# ES_Project.net
KiCad netlist of a schematic drawn in EasyEDA
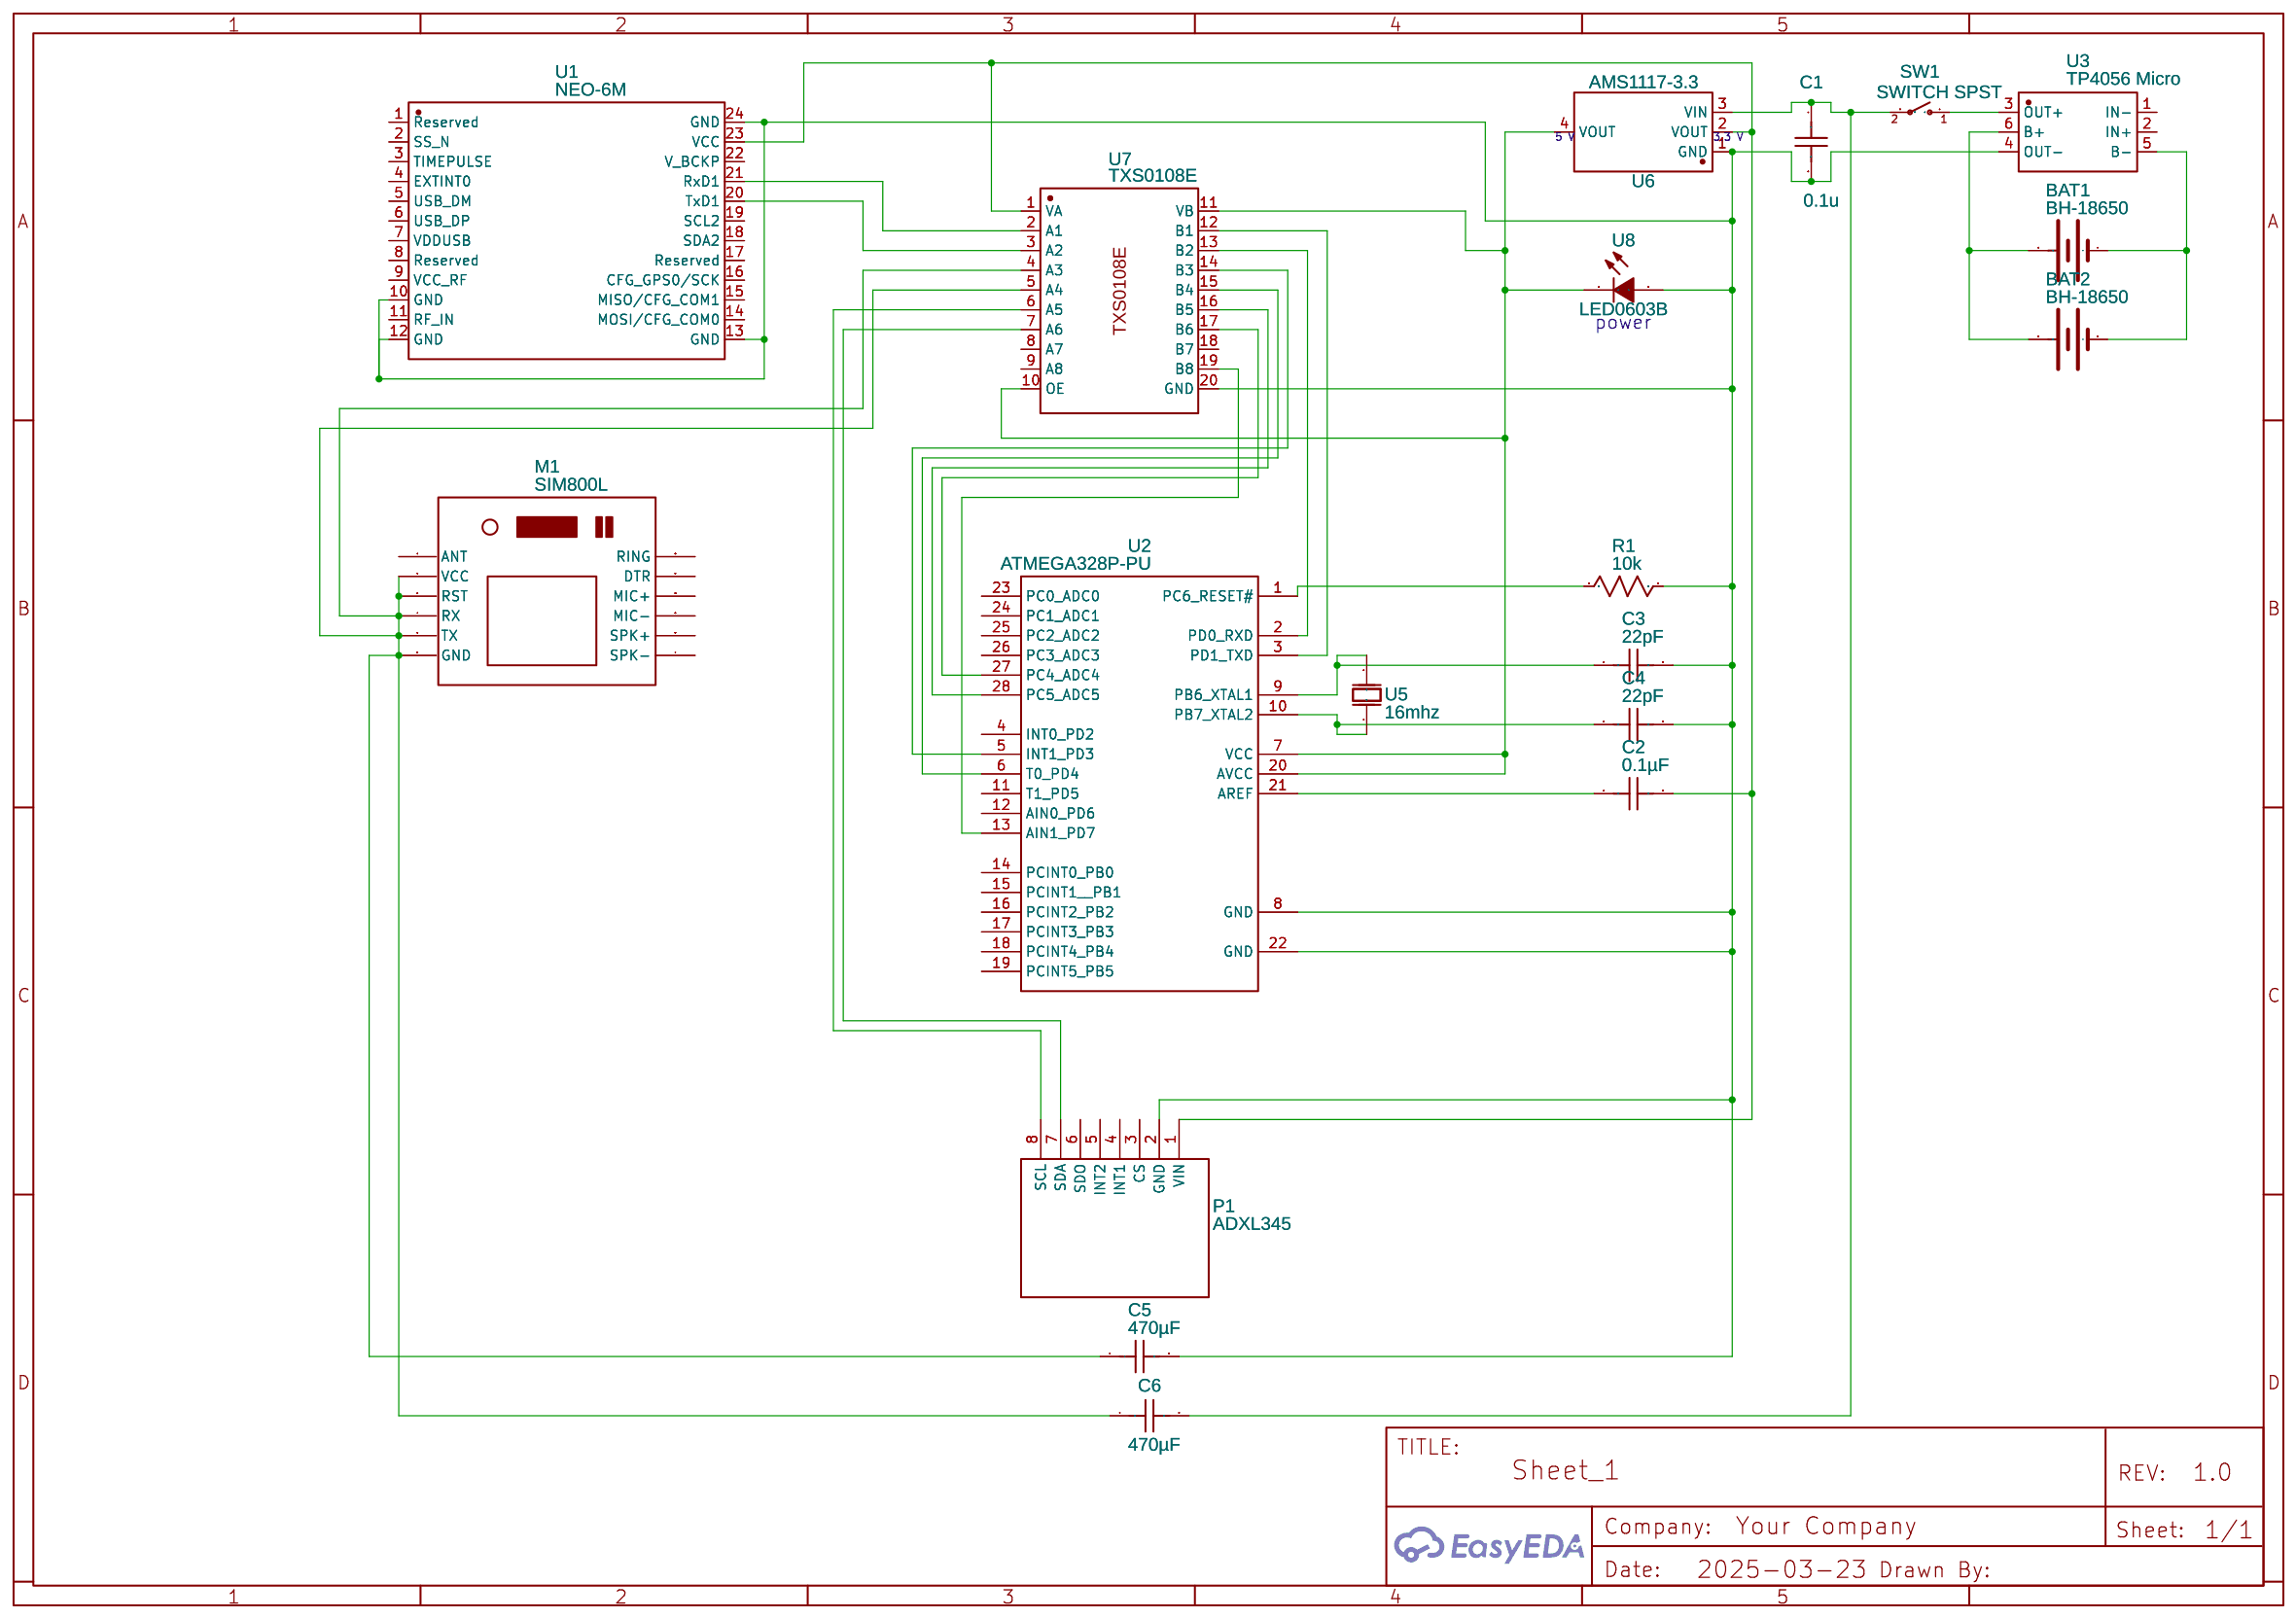
[diagram p0: schematic sheet]

(export (version "E")
  (design (tool "Eeschema 10.0.6"))
  (components
    (comp (ref "BAT1") (value "BH-18650") (libsource (lib "") (part "BH-18650")))
    (comp (ref "BAT2") (value "BH-18650") (libsource (lib "") (part "BH-18650")))
    (comp (ref "C1") (value "0.1u") (libsource (lib "") (part "C_0603_US_1")))
    (comp (ref "C2") (value "0.1µF") (libsource (lib "") (part "C_0603_US")))
    (comp (ref "C3") (value "22pF") (libsource (lib "") (part "C_0603_US")))
    (comp (ref "C4") (value "22pF") (libsource (lib "") (part "C_0603_US")))
    (comp (ref "C5") (value "470µF") (libsource (lib "") (part "C_0603_US")))
    (comp (ref "C6") (value "470µF") (libsource (lib "") (part "C_0603_US")))
    (comp (ref "M1") (value "SIM800L") (libsource (lib "") (part "SIM800L")))
    (comp (ref "P1") (value "ADXL345") (libsource (lib "") (part "ADXL345")))
    (comp (ref "R1") (value "10k") (libsource (lib "") (part "R_0603_US")))
    (comp (ref "SW1") (value "SWITCH SPST") (libsource (lib "") (part "SWITCH SPST")))
    (comp (ref "U1") (value "NEO-6M") (libsource (lib "") (part "NEO-6M")))
    (comp (ref "U2")
      (value "ATMEGA328P-PU")
      (fields (field (name "Manufacturer") "MICROCHIP(美国微芯)"))
      (libsource (lib "") (part "ATMEGA328P-PU"))
    )
    (comp (ref "U3") (value "TP4056 Micro") (libsource (lib "") (part "TP4056 Micro")))
    (comp (ref "U5") (value "16mhz") (libsource (lib "") (part "16MHZCRYSTAL")))
    (comp (ref "U6")
      (value "AMS1117-3.3")
      (fields (field (name "Manufacturer") "AMS"))
      (libsource (lib "") (part "AMS1117-3.3"))
    )
    (comp (ref "U7") (value "TXS0108E") (libsource (lib "") (part "TXS0108E")))
    (comp (ref "U8") (value "LED0603B") (libsource (lib "") (part "LED0603B")))
  )
  (nets
    (net (code "1") (name "Net-(BAT1-+)") (class "Default")
      (node (ref "BAT1") (pin "2") (pinfunction "+_2") (pintype "passive"))
      (node (ref "BAT2") (pin "2") (pinfunction "+_2") (pintype "passive"))
      (node (ref "U3") (pin "6") (pinfunction "B+_6") (pintype "output"))
    )
    (net (code "2") (name "Net-(BAT1--)") (class "Default")
      (node (ref "BAT1") (pin "1") (pinfunction "-_1") (pintype "passive"))
      (node (ref "BAT2") (pin "1") (pinfunction "-_1") (pintype "passive"))
      (node (ref "U3") (pin "5") (pinfunction "B-_5") (pintype "output"))
    )
    (net (code "3") (name "Net-(M1-GND)") (class "Default")
      (node (ref "C5") (pin "1") (pinfunction "1_1") (pintype "unspecified"))
      (node (ref "C6") (pin "1") (pinfunction "1_1") (pintype "unspecified"))
      (node (ref "M1") (pin "2") (pinfunction "VCC_2") (pintype "input"))
      (node (ref "M1") (pin "3") (pinfunction "RST_3") (pintype "input"))
      (node (ref "M1") (pin "4") (pinfunction "RX_4") (pintype "input"))
      (node (ref "M1") (pin "5") (pinfunction "TX_5") (pintype "output"))
      (node (ref "M1") (pin "6") (pinfunction "GND_6") (pintype "output"))
      (node (ref "U7") (pin "4") (pinfunction "A3_4") (pintype "unspecified"))
      (node (ref "U7") (pin "5") (pinfunction "A4_5") (pintype "unspecified"))
    )
    (net (code "4") (name "Net-(P1-GND)") (class "Default")
      (node (ref "C1") (pin "2") (pinfunction "2_2") (pintype "unspecified"))
      (node (ref "C3") (pin "2") (pinfunction "2_2") (pintype "unspecified"))
      (node (ref "C4") (pin "2") (pinfunction "2_2") (pintype "unspecified"))
      (node (ref "C5") (pin "2") (pinfunction "2_2") (pintype "unspecified"))
      (node (ref "P1") (pin "2") (pinfunction "GND_2") (pintype "unspecified"))
      (node (ref "R1") (pin "2") (pinfunction "2_2") (pintype "unspecified"))
      (node (ref "U1") (pin "10") (pinfunction "GND_10") (pintype "unspecified"))
      (node (ref "U1") (pin "12") (pinfunction "GND_12") (pintype "unspecified"))
      (node (ref "U1") (pin "13") (pinfunction "GND_13") (pintype "unspecified"))
      (node (ref "U1") (pin "24") (pinfunction "GND_24") (pintype "unspecified"))
      (node (ref "U2") (pin "22") (pinfunction "GND_22") (pintype "passive"))
      (node (ref "U2") (pin "8") (pinfunction "GND_8") (pintype "passive"))
      (node (ref "U3") (pin "4") (pinfunction "OUT-_4") (pintype "output"))
      (node (ref "U6") (pin "1") (pinfunction "GND_1") (pintype "unspecified"))
      (node (ref "U7") (pin "20") (pinfunction "GND_20") (pintype "unspecified"))
      (node (ref "U8") (pin "2") (pinfunction "A_2") (pintype "input"))
    )
    (net (code "5") (name "Net-(P1-SCL)") (class "Default")
      (node (ref "P1") (pin "8") (pinfunction "SCL_8") (pintype "unspecified"))
      (node (ref "U7") (pin "6") (pinfunction "A5_6") (pintype "unspecified"))
    )
    (net (code "6") (name "Net-(P1-SDA)") (class "Default")
      (node (ref "P1") (pin "7") (pinfunction "SDA_7") (pintype "unspecified"))
      (node (ref "U7") (pin "7") (pinfunction "A6_7") (pintype "unspecified"))
    )
    (net (code "7") (name "Net-(P1-VIN)") (class "Default")
      (node (ref "C2") (pin "2") (pinfunction "2_2") (pintype "unspecified"))
      (node (ref "P1") (pin "1") (pinfunction "VIN_1") (pintype "unspecified"))
      (node (ref "U1") (pin "23") (pinfunction "VCC_23") (pintype "unspecified"))
      (node (ref "U6") (pin "2") (pinfunction "VOUT_2") (pintype "unspecified"))
      (node (ref "U7") (pin "1") (pinfunction "VA_1") (pintype "unspecified"))
    )
    (net (code "8") (name "Net-(U1-RxD1)") (class "Default")
      (node (ref "U1") (pin "21") (pinfunction "RxD1_21") (pintype "unspecified"))
      (node (ref "U7") (pin "2") (pinfunction "A1_2") (pintype "unspecified"))
    )
    (net (code "9") (name "Net-(U1-TxD1)") (class "Default")
      (node (ref "U1") (pin "20") (pinfunction "TxD1_20") (pintype "unspecified"))
      (node (ref "U7") (pin "3") (pinfunction "A2_3") (pintype "unspecified"))
    )
    (net (code "10") (name "Net-(U2-AIN1_PD7)") (class "Default")
      (node (ref "U2") (pin "13") (pinfunction "AIN1_PD7_13") (pintype "bidirectional"))
      (node (ref "U7") (pin "19") (pinfunction "B8_19") (pintype "unspecified"))
    )
    (net (code "11") (name "Net-(U2-AREF)") (class "Default")
      (node (ref "C2") (pin "1") (pinfunction "1_1") (pintype "unspecified"))
      (node (ref "U2") (pin "21") (pinfunction "AREF_21") (pintype "passive"))
    )
    (net (code "12") (name "Net-(U2-AVCC)") (class "Default")
      (node (ref "U2") (pin "20") (pinfunction "AVCC_20") (pintype "passive"))
      (node (ref "U2") (pin "7") (pinfunction "VCC_7") (pintype "passive"))
      (node (ref "U6") (pin "4") (pinfunction "VOUT_4") (pintype "unspecified"))
      (node (ref "U7") (pin "10") (pinfunction "OE_10") (pintype "unspecified"))
      (node (ref "U7") (pin "11") (pinfunction "VB_11") (pintype "unspecified"))
      (node (ref "U8") (pin "1") (pinfunction "K_1") (pintype "input"))
    )
    (net (code "13") (name "Net-(U2-INT1_PD3)") (class "Default")
      (node (ref "U2") (pin "5") (pinfunction "INT1_PD3_5") (pintype "bidirectional"))
      (node (ref "U7") (pin "14") (pinfunction "B3_14") (pintype "unspecified"))
    )
    (net (code "14") (name "Net-(U2-PB6_XTAL1)") (class "Default")
      (node (ref "C3") (pin "1") (pinfunction "1_1") (pintype "unspecified"))
      (node (ref "U2") (pin "9") (pinfunction "PB6_XTAL1_9") (pintype "bidirectional"))
      (node (ref "U5") (pin "2") (pinfunction "2_2") (pintype "input"))
    )
    (net (code "15") (name "Net-(U2-PB7_XTAL2)") (class "Default")
      (node (ref "C4") (pin "1") (pinfunction "1_1") (pintype "unspecified"))
      (node (ref "U2") (pin "10") (pinfunction "PB7_XTAL2_10") (pintype "bidirectional"))
      (node (ref "U5") (pin "1") (pinfunction "1_1") (pintype "input"))
    )
    (net (code "16") (name "Net-(U2-PC4_ADC4)") (class "Default")
      (node (ref "U2") (pin "27") (pinfunction "PC4_ADC4_27") (pintype "bidirectional"))
      (node (ref "U7") (pin "17") (pinfunction "B6_17") (pintype "unspecified"))
    )
    (net (code "17") (name "Net-(U2-PC5_ADC5)") (class "Default")
      (node (ref "U2") (pin "28") (pinfunction "PC5_ADC5_28") (pintype "bidirectional"))
      (node (ref "U7") (pin "16") (pinfunction "B5_16") (pintype "unspecified"))
    )
    (net (code "18") (name "Net-(U2-PC6_RESET#)") (class "Default")
      (node (ref "R1") (pin "1") (pinfunction "1_1") (pintype "unspecified"))
      (node (ref "U2") (pin "1") (pinfunction "PC6_RESET#_1") (pintype "bidirectional"))
    )
    (net (code "19") (name "Net-(U2-PD0_RXD)") (class "Default")
      (node (ref "U2") (pin "2") (pinfunction "PD0_RXD_2") (pintype "bidirectional"))
      (node (ref "U7") (pin "13") (pinfunction "B2_13") (pintype "unspecified"))
    )
    (net (code "20") (name "Net-(U2-PD1_TXD)") (class "Default")
      (node (ref "U2") (pin "3") (pinfunction "PD1_TXD_3") (pintype "bidirectional"))
      (node (ref "U7") (pin "12") (pinfunction "B1_12") (pintype "unspecified"))
    )
    (net (code "21") (name "Net-(U2-T0_PD4)") (class "Default")
      (node (ref "U2") (pin "6") (pinfunction "T0_PD4_6") (pintype "bidirectional"))
      (node (ref "U7") (pin "15") (pinfunction "B4_15") (pintype "unspecified"))
    )
    (net (code "22") (name "Net-(U3-OUT+)") (class "Default")
      (node (ref "SW1") (pin "1") (pinfunction "1_1") (pintype "unspecified"))
      (node (ref "U3") (pin "3") (pinfunction "OUT+_3") (pintype "output"))
    )
    (net (code "23") (name "Net-(U6-VIN)") (class "Default")
      (node (ref "C1") (pin "1") (pinfunction "1_1") (pintype "unspecified"))
      (node (ref "C6") (pin "2") (pinfunction "2_2") (pintype "unspecified"))
      (node (ref "SW1") (pin "2") (pinfunction "2_2") (pintype "unspecified"))
      (node (ref "U6") (pin "3") (pinfunction "VIN_3") (pintype "unspecified"))
    )
    (net (code "24") (name "unconnected-(M1-ANT-Pad1)") (class "Default")
      (node (ref "M1") (pin "1") (pinfunction "ANT_1") (pintype "output"))
    )
    (net (code "25") (name "unconnected-(M1-DTR-Pad11)") (class "Default")
      (node (ref "M1") (pin "11") (pinfunction "DTR_11") (pintype "output"))
    )
    (net (code "26") (name "unconnected-(M1-MIC+-Pad10)") (class "Default")
      (node (ref "M1") (pin "10") (pinfunction "MIC+_10") (pintype "input"))
    )
    (net (code "27") (name "unconnected-(M1-MIC--Pad9)") (class "Default")
      (node (ref "M1") (pin "9") (pinfunction "MIC-_9") (pintype "input"))
    )
    (net (code "28") (name "unconnected-(M1-RING-Pad12)") (class "Default")
      (node (ref "M1") (pin "12") (pinfunction "RING_12") (pintype "output"))
    )
    (net (code "29") (name "unconnected-(M1-SPK+-Pad8)") (class "Default")
      (node (ref "M1") (pin "8") (pinfunction "SPK+_8") (pintype "output"))
    )
    (net (code "30") (name "unconnected-(M1-SPK--Pad7)") (class "Default")
      (node (ref "M1") (pin "7") (pinfunction "SPK-_7") (pintype "output"))
    )
    (net (code "31") (name "unconnected-(P1-CS-Pad3)") (class "Default")
      (node (ref "P1") (pin "3") (pinfunction "CS_3") (pintype "unspecified"))
    )
    (net (code "32") (name "unconnected-(P1-INT1-Pad4)") (class "Default")
      (node (ref "P1") (pin "4") (pinfunction "INT1_4") (pintype "unspecified"))
    )
    (net (code "33") (name "unconnected-(P1-INT2-Pad5)") (class "Default")
      (node (ref "P1") (pin "5") (pinfunction "INT2_5") (pintype "unspecified"))
    )
    (net (code "34") (name "unconnected-(P1-SDO-Pad6)") (class "Default")
      (node (ref "P1") (pin "6") (pinfunction "SDO_6") (pintype "unspecified"))
    )
    (net (code "35") (name "unconnected-(U1-CFG_GPS0{slash}SCK-Pad16)") (class "Default")
      (node (ref "U1") (pin "16") (pinfunction "CFG_GPS0/SCK_16") (pintype "unspecified"))
    )
    (net (code "36") (name "unconnected-(U1-EXTINT0-Pad4)") (class "Default")
      (node (ref "U1") (pin "4") (pinfunction "EXTINT0_4") (pintype "unspecified"))
    )
    (net (code "37") (name "unconnected-(U1-MISO{slash}CFG_COM1-Pad15)") (class "Default")
      (node (ref "U1") (pin "15") (pinfunction "MISO/CFG_COM1_15") (pintype "unspecified"))
    )
    (net (code "38") (name "unconnected-(U1-MOSI{slash}CFG_COM0-Pad14)") (class "Default")
      (node (ref "U1") (pin "14") (pinfunction "MOSI/CFG_COM0_14") (pintype "unspecified"))
    )
    (net (code "39") (name "unconnected-(U1-RF_IN-Pad11)") (class "Default")
      (node (ref "U1") (pin "11") (pinfunction "RF_IN_11") (pintype "unspecified"))
    )
    (net (code "40") (name "unconnected-(U1-Reserved-Pad1)") (class "Default")
      (node (ref "U1") (pin "1") (pinfunction "Reserved_1") (pintype "unspecified"))
    )
    (net (code "41") (name "unconnected-(U1-Reserved-Pad8)") (class "Default")
      (node (ref "U1") (pin "8") (pinfunction "Reserved_8") (pintype "unspecified"))
    )
    (net (code "42") (name "unconnected-(U1-Reserved-Pad17)") (class "Default")
      (node (ref "U1") (pin "17") (pinfunction "Reserved_17") (pintype "unspecified"))
    )
    (net (code "43") (name "unconnected-(U1-SCL2-Pad19)") (class "Default")
      (node (ref "U1") (pin "19") (pinfunction "SCL2_19") (pintype "unspecified"))
    )
    (net (code "44") (name "unconnected-(U1-SDA2-Pad18)") (class "Default")
      (node (ref "U1") (pin "18") (pinfunction "SDA2_18") (pintype "unspecified"))
    )
    (net (code "45") (name "unconnected-(U1-SS_N-Pad2)") (class "Default")
      (node (ref "U1") (pin "2") (pinfunction "SS_N_2") (pintype "unspecified"))
    )
    (net (code "46") (name "unconnected-(U1-TIMEPULSE-Pad3)") (class "Default")
      (node (ref "U1") (pin "3") (pinfunction "TIMEPULSE_3") (pintype "unspecified"))
    )
    (net (code "47") (name "unconnected-(U1-USB_DM-Pad5)") (class "Default")
      (node (ref "U1") (pin "5") (pinfunction "USB_DM_5") (pintype "unspecified"))
    )
    (net (code "48") (name "unconnected-(U1-USB_DP-Pad6)") (class "Default")
      (node (ref "U1") (pin "6") (pinfunction "USB_DP_6") (pintype "unspecified"))
    )
    (net (code "49") (name "unconnected-(U1-VCC_RF-Pad9)") (class "Default")
      (node (ref "U1") (pin "9") (pinfunction "VCC_RF_9") (pintype "unspecified"))
    )
    (net (code "50") (name "unconnected-(U1-VDDUSB-Pad7)") (class "Default")
      (node (ref "U1") (pin "7") (pinfunction "VDDUSB_7") (pintype "unspecified"))
    )
    (net (code "51") (name "unconnected-(U1-V_BCKP-Pad22)") (class "Default")
      (node (ref "U1") (pin "22") (pinfunction "V_BCKP_22") (pintype "unspecified"))
    )
    (net (code "52") (name "unconnected-(U2-AIN0_PD6-Pad12)") (class "Default")
      (node (ref "U2") (pin "12") (pinfunction "AIN0_PD6_12") (pintype "bidirectional"))
    )
    (net (code "53") (name "unconnected-(U2-INT0_PD2-Pad4)") (class "Default")
      (node (ref "U2") (pin "4") (pinfunction "INT0_PD2_4") (pintype "bidirectional"))
    )
    (net (code "54") (name "unconnected-(U2-PC0_ADC0-Pad23)") (class "Default")
      (node (ref "U2") (pin "23") (pinfunction "PC0_ADC0_23") (pintype "bidirectional"))
    )
    (net (code "55") (name "unconnected-(U2-PC1_ADC1-Pad24)") (class "Default")
      (node (ref "U2") (pin "24") (pinfunction "PC1_ADC1_24") (pintype "bidirectional"))
    )
    (net (code "56") (name "unconnected-(U2-PC2_ADC2-Pad25)") (class "Default")
      (node (ref "U2") (pin "25") (pinfunction "PC2_ADC2_25") (pintype "bidirectional"))
    )
    (net (code "57") (name "unconnected-(U2-PC3_ADC3-Pad26)") (class "Default")
      (node (ref "U2") (pin "26") (pinfunction "PC3_ADC3_26") (pintype "bidirectional"))
    )
    (net (code "58") (name "unconnected-(U2-PCINT0_PB0-Pad14)") (class "Default")
      (node (ref "U2") (pin "14") (pinfunction "PCINT0_PB0_14") (pintype "bidirectional"))
    )
    (net (code "59") (name "unconnected-(U2-PCINT1__PB1-Pad15)") (class "Default")
      (node (ref "U2") (pin "15") (pinfunction "PCINT1__PB1_15") (pintype "bidirectional"))
    )
    (net (code "60") (name "unconnected-(U2-PCINT2_PB2-Pad16)") (class "Default")
      (node (ref "U2") (pin "16") (pinfunction "PCINT2_PB2_16") (pintype "bidirectional"))
    )
    (net (code "61") (name "unconnected-(U2-PCINT3_PB3-Pad17)") (class "Default")
      (node (ref "U2") (pin "17") (pinfunction "PCINT3_PB3_17") (pintype "bidirectional"))
    )
    (net (code "62") (name "unconnected-(U2-PCINT4_PB4-Pad18)") (class "Default")
      (node (ref "U2") (pin "18") (pinfunction "PCINT4_PB4_18") (pintype "bidirectional"))
    )
    (net (code "63") (name "unconnected-(U2-PCINT5_PB5-Pad19)") (class "Default")
      (node (ref "U2") (pin "19") (pinfunction "PCINT5_PB5_19") (pintype "bidirectional"))
    )
    (net (code "64") (name "unconnected-(U2-T1_PD5-Pad11)") (class "Default")
      (node (ref "U2") (pin "11") (pinfunction "T1_PD5_11") (pintype "bidirectional"))
    )
    (net (code "65") (name "unconnected-(U3-IN+-Pad2)") (class "Default")
      (node (ref "U3") (pin "2") (pinfunction "IN+_2") (pintype "input"))
    )
    (net (code "66") (name "unconnected-(U3-IN--Pad1)") (class "Default")
      (node (ref "U3") (pin "1") (pinfunction "IN-_1") (pintype "input"))
    )
    (net (code "67") (name "unconnected-(U7-A7-Pad8)") (class "Default")
      (node (ref "U7") (pin "8") (pinfunction "A7_8") (pintype "unspecified"))
    )
    (net (code "68") (name "unconnected-(U7-A8-Pad9)") (class "Default")
      (node (ref "U7") (pin "9") (pinfunction "A8_9") (pintype "unspecified"))
    )
    (net (code "69") (name "unconnected-(U7-B7-Pad18)") (class "Default")
      (node (ref "U7") (pin "18") (pinfunction "B7_18") (pintype "unspecified"))
    )
  )
)
